# 6.net
KiCad netlist of a schematic drawn in Altium Designer
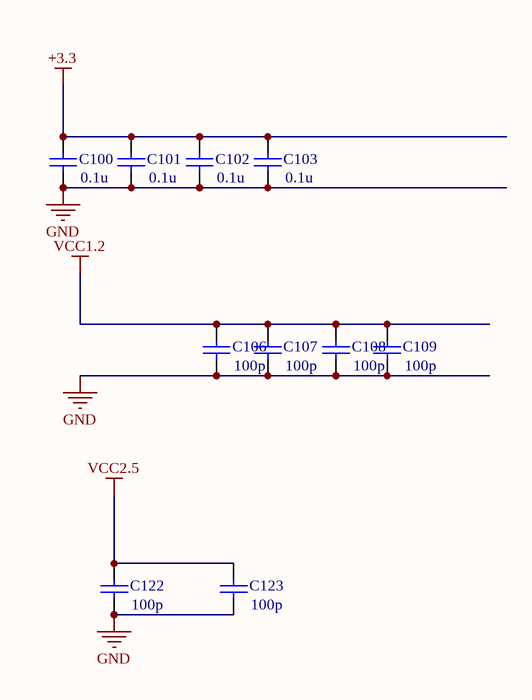
[diagram p0: 示波器原理图6.SchDoc]

(export (version "E")
  (design (tool "Eeschema 10.0.6"))
  (components
    (comp (ref "C100")
      (value "0.1u")
      (footprint "0805封装:PCBComponent_1")
      (description "Capacitor (Semiconductor SIM Model)")
      (fields (field (name "PUBLISHER") "Altium Limited"))
      (libsource (lib "Miscellaneous Devices") (part "Cap Semi"))
    )
    (comp (ref "C101")
      (value "0.1u")
      (footprint "0805封装:PCBComponent_1")
      (description "Capacitor (Semiconductor SIM Model)")
      (fields (field (name "PUBLISHER") "Altium Limited"))
      (libsource (lib "Miscellaneous Devices") (part "Cap Semi"))
    )
    (comp (ref "C102")
      (value "0.1u")
      (footprint "0805封装:PCBComponent_1")
      (description "Capacitor (Semiconductor SIM Model)")
      (fields (field (name "PUBLISHER") "Altium Limited"))
      (libsource (lib "Miscellaneous Devices") (part "Cap Semi"))
    )
    (comp (ref "C103")
      (value "0.1u")
      (footprint "0805封装:PCBComponent_1")
      (description "Capacitor (Semiconductor SIM Model)")
      (fields (field (name "PUBLISHER") "Altium Limited"))
      (libsource (lib "Miscellaneous Devices") (part "Cap Semi"))
    )
    (comp (ref "C106")
      (value "100p")
      (footprint "0805封装:PCBComponent_1")
      (description "Capacitor (Semiconductor SIM Model)")
      (fields (field (name "PUBLISHER") "Altium Limited"))
      (libsource (lib "Miscellaneous Devices") (part "Cap Semi"))
    )
    (comp (ref "C107")
      (value "100p")
      (footprint "0805封装:PCBComponent_1")
      (description "Capacitor (Semiconductor SIM Model)")
      (fields (field (name "PUBLISHER") "Altium Limited"))
      (libsource (lib "Miscellaneous Devices") (part "Cap Semi"))
    )
    (comp (ref "C108")
      (value "100p")
      (footprint "0805封装:PCBComponent_1")
      (description "Capacitor (Semiconductor SIM Model)")
      (fields (field (name "PUBLISHER") "Altium Limited"))
      (libsource (lib "Miscellaneous Devices") (part "Cap Semi"))
    )
    (comp (ref "C109")
      (value "100p")
      (footprint "0805封装:PCBComponent_1")
      (description "Capacitor (Semiconductor SIM Model)")
      (fields (field (name "PUBLISHER") "Altium Limited"))
      (libsource (lib "Miscellaneous Devices") (part "Cap Semi"))
    )
    (comp (ref "C122")
      (value "100p")
      (footprint "0805封装:PCBComponent_1")
      (description "Capacitor (Semiconductor SIM Model)")
      (fields (field (name "PUBLISHER") "Altium Limited"))
      (libsource (lib "Miscellaneous Devices") (part "Cap Semi"))
    )
    (comp (ref "C123")
      (value "100p")
      (footprint "0805封装:PCBComponent_1")
      (description "Capacitor (Semiconductor SIM Model)")
      (fields (field (name "PUBLISHER") "Altium Limited"))
      (libsource (lib "Miscellaneous Devices") (part "Cap Semi"))
    )
  )
  (nets
    (net (code "1") (name "+3.3") (class "Default")
      (node (ref "C100") (pin "2") (pinfunction "2_2") (pintype "passive"))
      (node (ref "C101") (pin "2") (pinfunction "2_2") (pintype "passive"))
      (node (ref "C102") (pin "2") (pinfunction "2_2") (pintype "passive"))
      (node (ref "C103") (pin "2") (pinfunction "2_2") (pintype "passive"))
    )
    (net (code "2") (name "GND") (class "Default")
      (node (ref "C100") (pin "1") (pinfunction "1_1") (pintype "passive"))
      (node (ref "C101") (pin "1") (pinfunction "1_1") (pintype "passive"))
      (node (ref "C102") (pin "1") (pinfunction "1_1") (pintype "passive"))
      (node (ref "C103") (pin "1") (pinfunction "1_1") (pintype "passive"))
      (node (ref "C106") (pin "1") (pinfunction "1_1") (pintype "passive"))
      (node (ref "C107") (pin "1") (pinfunction "1_1") (pintype "passive"))
      (node (ref "C108") (pin "1") (pinfunction "1_1") (pintype "passive"))
      (node (ref "C109") (pin "1") (pinfunction "1_1") (pintype "passive"))
      (node (ref "C122") (pin "1") (pinfunction "1_1") (pintype "passive"))
      (node (ref "C123") (pin "1") (pinfunction "1_1") (pintype "passive"))
    )
    (net (code "3") (name "VCC1.2") (class "Default")
      (node (ref "C106") (pin "2") (pinfunction "2_2") (pintype "passive"))
      (node (ref "C107") (pin "2") (pinfunction "2_2") (pintype "passive"))
      (node (ref "C108") (pin "2") (pinfunction "2_2") (pintype "passive"))
      (node (ref "C109") (pin "2") (pinfunction "2_2") (pintype "passive"))
    )
    (net (code "4") (name "VCC2.5") (class "Default")
      (node (ref "C122") (pin "2") (pinfunction "2_2") (pintype "passive"))
      (node (ref "C123") (pin "2") (pinfunction "2_2") (pintype "passive"))
    )
  )
)
